# MainPCB.net
KiCad netlist of a schematic drawn in Altium Designer
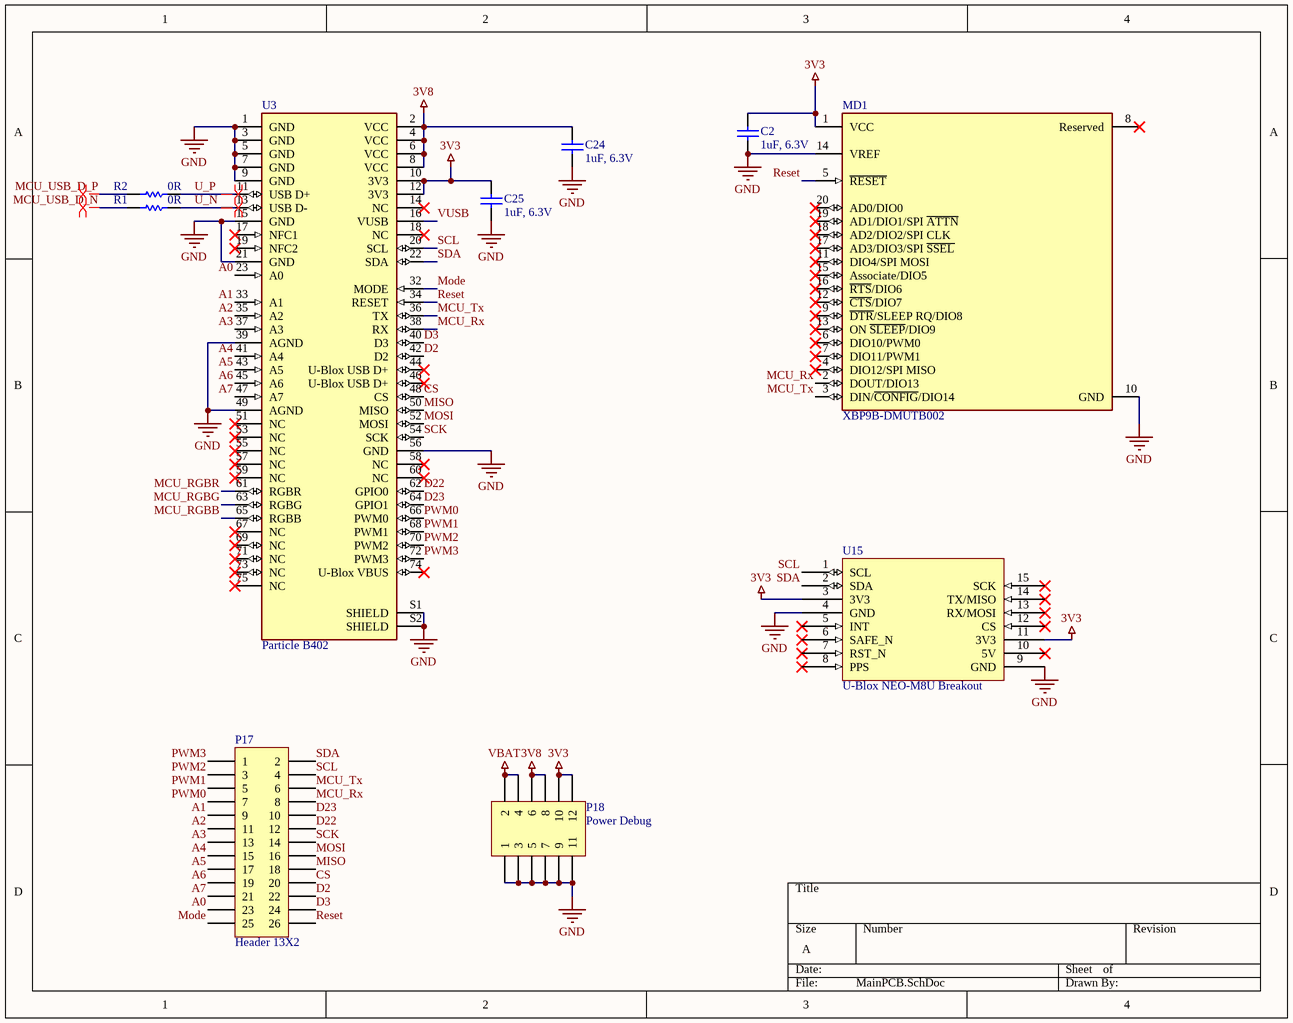
[diagram p0: MainPCB.SchDoc]

(export (version "E")
  (design (tool "Eeschema 10.0.6"))
  (components
    (comp (ref "C2")
      (value "1uF, 6.3V")
      (footprint "ANTC1608X90N")
      (description "Capacitor")
      (libsource (lib "Simulation Generic Components") (part "Capacitor"))
    )
    (comp (ref "C24")
      (value "1uF, 6.3V")
      (footprint "ANTC1608X90N")
      (description "Capacitor")
      (libsource (lib "Simulation Generic Components") (part "Capacitor"))
    )
    (comp (ref "C25")
      (value "1uF, 6.3V")
      (footprint "ANTC1608X90N")
      (description "Capacitor")
      (libsource (lib "Simulation Generic Components") (part "Capacitor"))
    )
    (comp (ref "MD1")
      (value "XBP9B-DMUTB002")
      (footprint "FP-XBP9B-DMUTB002-MFG")
      (description "RX TXRX MOD ISM < 1GHZ U.FL TH")
      (libsource (lib "Altium Content Vault") (part "053d8e65a610ce00d52093c0e212ca3"))
    )
    (comp (ref "P17")
      (value "Header 13X2")
      (footprint "HDR2X13")
      (description "Header, 13-Pin, Dual row")
      (fields (field (name "PUBLISHER") "Altium Limited"))
      (libsource (lib "Miscellaneous Connectors") (part "Header 13X2"))
    )
    (comp (ref "P18")
      (value "Power Debug")
      (footprint "HDR2X6")
      (description "Header, 6-Pin, Dual row")
      (fields (field (name "PUBLISHER") "Altium Limited"))
      (libsource (lib "Miscellaneous Connectors") (part "Header 6X2"))
    )
    (comp (ref "R1")
      (value "0R")
      (footprint "0603 Resistor")
      (description "Resistor")
      (libsource (lib "Simulation Generic Components") (part "Resistor"))
    )
    (comp (ref "R2")
      (value "0R")
      (footprint "0603 Resistor")
      (description "Resistor")
      (libsource (lib "Simulation Generic Components") (part "Resistor"))
    )
    (comp (ref "U3")
      (value "B402")
      (footprint "B402 Full")
      (description "Connector, Backplane, Housing, Receptacle, 67 Position, 2row")
      (fields (field (name "MP") "2199230-4") (field (name "SUPPLIER PART NUMBER 1") "Particle B402"))
      (libsource (lib "WaterNet23BotPCB") (part "B402"))
    )
    (comp (ref "U15")
      (value "U-Blox NEO-M8U Breakout")
      (footprint "U-Blox NEO-M8U")
      (description "GPS Board")
      (libsource (lib "WaterNet23BotPCB") (part "U-Blox NEO-M8U Breakout"))
    )
  )
  (nets
    (net (code "1") (name "/A0") (class "Default")
      (node (ref "P17") (pin "23") (pinfunction "23_23") (pintype "passive"))
      (node (ref "U3") (pin "23") (pinfunction "A0_23") (pintype "input"))
    )
    (net (code "2") (name "/A1") (class "Default")
      (node (ref "P17") (pin "9") (pinfunction "9_9") (pintype "passive"))
      (node (ref "U3") (pin "33") (pinfunction "A1_33") (pintype "input"))
    )
    (net (code "3") (name "/A2") (class "Default")
      (node (ref "P17") (pin "11") (pinfunction "11_11") (pintype "passive"))
      (node (ref "U3") (pin "35") (pinfunction "A2_35") (pintype "input"))
    )
    (net (code "4") (name "/A3") (class "Default")
      (node (ref "P17") (pin "13") (pinfunction "13_13") (pintype "passive"))
      (node (ref "U3") (pin "37") (pinfunction "A3_37") (pintype "input"))
    )
    (net (code "5") (name "/A4") (class "Default")
      (node (ref "P17") (pin "15") (pinfunction "15_15") (pintype "passive"))
      (node (ref "U3") (pin "41") (pinfunction "A4_41") (pintype "input"))
    )
    (net (code "6") (name "/A5") (class "Default")
      (node (ref "P17") (pin "17") (pinfunction "17_17") (pintype "passive"))
      (node (ref "U3") (pin "43") (pinfunction "A5_43") (pintype "input"))
    )
    (net (code "7") (name "/A6") (class "Default")
      (node (ref "P17") (pin "19") (pinfunction "19_19") (pintype "passive"))
      (node (ref "U3") (pin "45") (pinfunction "A6_45") (pintype "input"))
    )
    (net (code "8") (name "/A7") (class "Default")
      (node (ref "P17") (pin "21") (pinfunction "21_21") (pintype "passive"))
      (node (ref "U3") (pin "47") (pinfunction "A7_47") (pintype "input"))
    )
    (net (code "9") (name "/CS") (class "Default")
      (node (ref "P17") (pin "20") (pinfunction "20_20") (pintype "passive"))
      (node (ref "U3") (pin "48") (pinfunction "CS_48") (pintype "bidirectional"))
    )
    (net (code "10") (name "/D2") (class "Default")
      (node (ref "P17") (pin "22") (pinfunction "22_22") (pintype "passive"))
      (node (ref "U3") (pin "42") (pinfunction "D2_42") (pintype "bidirectional"))
    )
    (net (code "11") (name "/D3") (class "Default")
      (node (ref "P17") (pin "24") (pinfunction "24_24") (pintype "passive"))
      (node (ref "U3") (pin "40") (pinfunction "D3_40") (pintype "bidirectional"))
    )
    (net (code "12") (name "/D22") (class "Default")
      (node (ref "P17") (pin "12") (pinfunction "12_12") (pintype "passive"))
      (node (ref "U3") (pin "62") (pinfunction "GPIO0_62") (pintype "bidirectional"))
    )
    (net (code "13") (name "/D23") (class "Default")
      (node (ref "P17") (pin "10") (pinfunction "10_10") (pintype "passive"))
      (node (ref "U3") (pin "64") (pinfunction "GPIO1_64") (pintype "bidirectional"))
    )
    (net (code "14") (name "/MCU_RGBB") (class "Default")
      (node (ref "U3") (pin "65") (pinfunction "RGBB_65") (pintype "bidirectional"))
    )
    (net (code "15") (name "/MCU_RGBG") (class "Default")
      (node (ref "U3") (pin "63") (pinfunction "RGBG_63") (pintype "bidirectional"))
    )
    (net (code "16") (name "/MCU_RGBR") (class "Default")
      (node (ref "U3") (pin "61") (pinfunction "RGBR_61") (pintype "bidirectional"))
    )
    (net (code "17") (name "/MCU_Rx") (class "Default")
      (node (ref "MD1") (pin "2") (pinfunction "DOUT/DIO13_2") (pintype "bidirectional"))
      (node (ref "P17") (pin "8") (pinfunction "8_8") (pintype "passive"))
      (node (ref "U3") (pin "38") (pinfunction "RX_38") (pintype "bidirectional"))
    )
    (net (code "18") (name "/MCU_Tx") (class "Default")
      (node (ref "MD1") (pin "3") (pinfunction "DIN/~{CONFIG}/DIO14_3") (pintype "bidirectional"))
      (node (ref "P17") (pin "6") (pinfunction "6_6") (pintype "passive"))
      (node (ref "U3") (pin "36") (pinfunction "TX_36") (pintype "bidirectional"))
    )
    (net (code "19") (name "/MCU_USB_D_N") (class "Default")
      (node (ref "R1") (pin "1") (pinfunction "1_1") (pintype "passive"))
    )
    (net (code "20") (name "/MCU_USB_D_P") (class "Default")
      (node (ref "R2") (pin "1") (pinfunction "1_1") (pintype "passive"))
    )
    (net (code "21") (name "/MISO") (class "Default")
      (node (ref "P17") (pin "18") (pinfunction "18_18") (pintype "passive"))
      (node (ref "U3") (pin "50") (pinfunction "MISO_50") (pintype "bidirectional"))
    )
    (net (code "22") (name "/MOSI") (class "Default")
      (node (ref "P17") (pin "16") (pinfunction "16_16") (pintype "passive"))
      (node (ref "U3") (pin "52") (pinfunction "MOSI_52") (pintype "bidirectional"))
    )
    (net (code "23") (name "/Mode") (class "Default")
      (node (ref "P17") (pin "25") (pinfunction "25_25") (pintype "passive"))
      (node (ref "U3") (pin "32") (pinfunction "MODE_32") (pintype "input"))
    )
    (net (code "24") (name "/PWM0") (class "Default")
      (node (ref "P17") (pin "7") (pinfunction "7_7") (pintype "passive"))
      (node (ref "U3") (pin "66") (pinfunction "PWM0_66") (pintype "bidirectional"))
    )
    (net (code "25") (name "/PWM1") (class "Default")
      (node (ref "P17") (pin "5") (pinfunction "5_5") (pintype "passive"))
      (node (ref "U3") (pin "68") (pinfunction "PWM1_68") (pintype "bidirectional"))
    )
    (net (code "26") (name "/PWM2") (class "Default")
      (node (ref "P17") (pin "3") (pinfunction "3_3") (pintype "passive"))
      (node (ref "U3") (pin "70") (pinfunction "PWM2_70") (pintype "bidirectional"))
    )
    (net (code "27") (name "/PWM3") (class "Default")
      (node (ref "P17") (pin "1") (pinfunction "1_1") (pintype "passive"))
      (node (ref "U3") (pin "72") (pinfunction "PWM3_72") (pintype "bidirectional"))
    )
    (net (code "28") (name "/Reset") (class "Default")
      (node (ref "MD1") (pin "5") (pinfunction "~{RESET}_5") (pintype "input"))
      (node (ref "P17") (pin "26") (pinfunction "26_26") (pintype "passive"))
      (node (ref "U3") (pin "34") (pinfunction "RESET_34") (pintype "input"))
    )
    (net (code "29") (name "/SCK") (class "Default")
      (node (ref "P17") (pin "14") (pinfunction "14_14") (pintype "passive"))
      (node (ref "U3") (pin "54") (pinfunction "SCK_54") (pintype "bidirectional"))
    )
    (net (code "30") (name "/SCL") (class "Default")
      (node (ref "P17") (pin "4") (pinfunction "4_4") (pintype "passive"))
      (node (ref "U15") (pin "1") (pinfunction "SCL_1") (pintype "bidirectional"))
      (node (ref "U3") (pin "20") (pinfunction "SCL_20") (pintype "bidirectional"))
    )
    (net (code "31") (name "/SDA") (class "Default")
      (node (ref "P17") (pin "2") (pinfunction "2_2") (pintype "passive"))
      (node (ref "U15") (pin "2") (pinfunction "SDA_2") (pintype "bidirectional"))
      (node (ref "U3") (pin "22") (pinfunction "SDA_22") (pintype "bidirectional"))
    )
    (net (code "32") (name "/U_N") (class "Default")
      (node (ref "R1") (pin "2") (pinfunction "2_2") (pintype "passive"))
      (node (ref "U3") (pin "13") (pinfunction "USB_D-_13") (pintype "bidirectional"))
    )
    (net (code "33") (name "/U_P") (class "Default")
      (node (ref "R2") (pin "2") (pinfunction "2_2") (pintype "passive"))
      (node (ref "U3") (pin "11") (pinfunction "USB_D+_11") (pintype "bidirectional"))
    )
    (net (code "34") (name "/VUSB") (class "Default")
      (node (ref "U3") (pin "16") (pinfunction "VUSB_16") (pintype "power_in"))
    )
    (net (code "35") (name "3V3") (class "Default")
      (node (ref "C2") (pin "2") (pinfunction "2_2") (pintype "passive"))
      (node (ref "C25") (pin "2") (pinfunction "2_2") (pintype "passive"))
      (node (ref "MD1") (pin "1") (pinfunction "VCC_1") (pintype "power_in"))
      (node (ref "P18") (pin "10") (pinfunction "10_10") (pintype "passive"))
      (node (ref "P18") (pin "12") (pinfunction "12_12") (pintype "passive"))
      (node (ref "U15") (pin "11") (pinfunction "3V3_11") (pintype "power_in"))
      (node (ref "U15") (pin "3") (pinfunction "3V3_3") (pintype "power_in"))
      (node (ref "U3") (pin "10") (pinfunction "3V3_10") (pintype "power_in"))
      (node (ref "U3") (pin "12") (pinfunction "3V3_12") (pintype "power_in"))
    )
    (net (code "36") (name "3V8") (class "Default")
      (node (ref "C24") (pin "2") (pinfunction "2_2") (pintype "passive"))
      (node (ref "P18") (pin "6") (pinfunction "6_6") (pintype "passive"))
      (node (ref "P18") (pin "8") (pinfunction "8_8") (pintype "passive"))
      (node (ref "U3") (pin "2") (pinfunction "VCC_2") (pintype "power_in"))
      (node (ref "U3") (pin "4") (pinfunction "VCC_4") (pintype "power_in"))
      (node (ref "U3") (pin "6") (pinfunction "VCC_6") (pintype "power_in"))
      (node (ref "U3") (pin "8") (pinfunction "VCC_8") (pintype "power_in"))
    )
    (net (code "37") (name "GND") (class "Default")
      (node (ref "C2") (pin "1") (pinfunction "1_1") (pintype "passive"))
      (node (ref "C24") (pin "1") (pinfunction "1_1") (pintype "passive"))
      (node (ref "C25") (pin "1") (pinfunction "1_1") (pintype "passive"))
      (node (ref "MD1") (pin "10") (pinfunction "GND_10") (pintype "power_in"))
      (node (ref "MD1") (pin "14") (pinfunction "VREF_14") (pintype "passive"))
      (node (ref "P18") (pin "1") (pinfunction "1_1") (pintype "passive"))
      (node (ref "P18") (pin "11") (pinfunction "11_11") (pintype "passive"))
      (node (ref "P18") (pin "3") (pinfunction "3_3") (pintype "passive"))
      (node (ref "P18") (pin "5") (pinfunction "5_5") (pintype "passive"))
      (node (ref "P18") (pin "7") (pinfunction "7_7") (pintype "passive"))
      (node (ref "P18") (pin "9") (pinfunction "9_9") (pintype "passive"))
      (node (ref "U15") (pin "4") (pinfunction "GND_4") (pintype "power_in"))
      (node (ref "U15") (pin "9") (pinfunction "GND_9") (pintype "power_in"))
      (node (ref "U3") (pin "1") (pinfunction "GND_1") (pintype "power_in"))
      (node (ref "U3") (pin "15") (pinfunction "GND_15") (pintype "power_in"))
      (node (ref "U3") (pin "21") (pinfunction "GND_21") (pintype "power_in"))
      (node (ref "U3") (pin "3") (pinfunction "GND_3") (pintype "power_in"))
      (node (ref "U3") (pin "39") (pinfunction "AGND_39") (pintype "power_in"))
      (node (ref "U3") (pin "49") (pinfunction "AGND_49") (pintype "power_in"))
      (node (ref "U3") (pin "5") (pinfunction "GND_5") (pintype "power_in"))
      (node (ref "U3") (pin "56") (pinfunction "GND_56") (pintype "power_in"))
      (node (ref "U3") (pin "7") (pinfunction "GND_7") (pintype "power_in"))
      (node (ref "U3") (pin "9") (pinfunction "GND_9") (pintype "power_in"))
      (node (ref "U3") (pin "S1") (pinfunction "SHIELD_S1") (pintype "passive"))
      (node (ref "U3") (pin "S2") (pinfunction "SHIELD_S2") (pintype "passive"))
    )
    (net (code "38") (name "VBAT") (class "Default")
      (node (ref "P18") (pin "2") (pinfunction "2_2") (pintype "passive"))
      (node (ref "P18") (pin "4") (pinfunction "4_4") (pintype "passive"))
    )
    (net (code "39") (name "unconnected-(MD1-AD0{slash}DIO0-Pad20)") (class "Default")
      (node (ref "MD1") (pin "20") (pinfunction "AD0/DIO0_20") (pintype "bidirectional+no_connect"))
    )
    (net (code "40") (name "unconnected-(MD1-AD1{slash}DIO1{slash}SPI_~{ATTN}-Pad19)") (class "Default")
      (node (ref "MD1") (pin "19") (pinfunction "AD1/DIO1/SPI_~{ATTN}_19") (pintype "bidirectional+no_connect"))
    )
    (net (code "41") (name "unconnected-(MD1-AD2{slash}DIO2{slash}SPI_CLK-Pad18)") (class "Default")
      (node (ref "MD1") (pin "18") (pinfunction "AD2/DIO2/SPI_CLK_18") (pintype "bidirectional+no_connect"))
    )
    (net (code "42") (name "unconnected-(MD1-AD3{slash}DIO3{slash}SPI_~{SSEL}-Pad17)") (class "Default")
      (node (ref "MD1") (pin "17") (pinfunction "AD3/DIO3/SPI_~{SSEL}_17") (pintype "bidirectional+no_connect"))
    )
    (net (code "43") (name "unconnected-(MD1-Associate{slash}DIO5-Pad15)") (class "Default")
      (node (ref "MD1") (pin "15") (pinfunction "Associate/DIO5_15") (pintype "bidirectional+no_connect"))
    )
    (net (code "44") (name "unconnected-(MD1-DIO4{slash}SPI_MOSI-Pad11)") (class "Default")
      (node (ref "MD1") (pin "11") (pinfunction "DIO4/SPI_MOSI_11") (pintype "bidirectional+no_connect"))
    )
    (net (code "45") (name "unconnected-(MD1-DIO10{slash}PWM0-Pad6)") (class "Default")
      (node (ref "MD1") (pin "6") (pinfunction "DIO10/PWM0_6") (pintype "bidirectional+no_connect"))
    )
    (net (code "46") (name "unconnected-(MD1-DIO11{slash}PWM1-Pad7)") (class "Default")
      (node (ref "MD1") (pin "7") (pinfunction "DIO11/PWM1_7") (pintype "bidirectional+no_connect"))
    )
    (net (code "47") (name "unconnected-(MD1-DIO12{slash}SPI_MISO-Pad4)") (class "Default")
      (node (ref "MD1") (pin "4") (pinfunction "DIO12/SPI_MISO_4") (pintype "bidirectional+no_connect"))
    )
    (net (code "48") (name "unconnected-(MD1-ON_~{SLEEP}{slash}DIO9-Pad13)") (class "Default")
      (node (ref "MD1") (pin "13") (pinfunction "ON_~{SLEEP}/DIO9_13") (pintype "bidirectional+no_connect"))
    )
    (net (code "49") (name "unconnected-(MD1-Reserved-Pad8)") (class "Default")
      (node (ref "MD1") (pin "8") (pinfunction "Reserved_8") (pintype "passive+no_connect"))
    )
    (net (code "50") (name "unconnected-(MD1-~{CTS}{slash}DIO7-Pad12)") (class "Default")
      (node (ref "MD1") (pin "12") (pinfunction "~{CTS}/DIO7_12") (pintype "bidirectional+no_connect"))
    )
    (net (code "51") (name "unconnected-(MD1-~{DTR}{slash}SLEEP_RQ{slash}DIO8-Pad9)") (class "Default")
      (node (ref "MD1") (pin "9") (pinfunction "~{DTR}/SLEEP_RQ/DIO8_9") (pintype "bidirectional+no_connect"))
    )
    (net (code "52") (name "unconnected-(MD1-~{RTS}{slash}DIO6-Pad16)") (class "Default")
      (node (ref "MD1") (pin "16") (pinfunction "~{RTS}/DIO6_16") (pintype "bidirectional+no_connect"))
    )
    (net (code "53") (name "unconnected-(U3-NC-Pad14)") (class "Default")
      (node (ref "U3") (pin "14") (pinfunction "NC_14") (pintype "tri_state+no_connect"))
    )
    (net (code "54") (name "unconnected-(U3-NC-Pad18)") (class "Default")
      (node (ref "U3") (pin "18") (pinfunction "NC_18") (pintype "tri_state+no_connect"))
    )
    (net (code "55") (name "unconnected-(U3-NC-Pad51)") (class "Default")
      (node (ref "U3") (pin "51") (pinfunction "NC_51") (pintype "tri_state+no_connect"))
    )
    (net (code "56") (name "unconnected-(U3-NC-Pad53)") (class "Default")
      (node (ref "U3") (pin "53") (pinfunction "NC_53") (pintype "tri_state+no_connect"))
    )
    (net (code "57") (name "unconnected-(U3-NC-Pad55)") (class "Default")
      (node (ref "U3") (pin "55") (pinfunction "NC_55") (pintype "tri_state+no_connect"))
    )
    (net (code "58") (name "unconnected-(U3-NC-Pad57)") (class "Default")
      (node (ref "U3") (pin "57") (pinfunction "NC_57") (pintype "tri_state+no_connect"))
    )
    (net (code "59") (name "unconnected-(U3-NC-Pad58)") (class "Default")
      (node (ref "U3") (pin "58") (pinfunction "NC_58") (pintype "tri_state+no_connect"))
    )
    (net (code "60") (name "unconnected-(U3-NC-Pad59)") (class "Default")
      (node (ref "U3") (pin "59") (pinfunction "NC_59") (pintype "tri_state+no_connect"))
    )
    (net (code "61") (name "unconnected-(U3-NC-Pad60)") (class "Default")
      (node (ref "U3") (pin "60") (pinfunction "NC_60") (pintype "tri_state+no_connect"))
    )
    (net (code "62") (name "unconnected-(U3-NC-Pad67)") (class "Default")
      (node (ref "U3") (pin "67") (pinfunction "NC_67") (pintype "power_in+no_connect"))
    )
    (net (code "63") (name "unconnected-(U3-NC-Pad69)") (class "Default")
      (node (ref "U3") (pin "69") (pinfunction "NC_69") (pintype "bidirectional+no_connect"))
    )
    (net (code "64") (name "unconnected-(U3-NC-Pad71)") (class "Default")
      (node (ref "U3") (pin "71") (pinfunction "NC_71") (pintype "bidirectional+no_connect"))
    )
    (net (code "65") (name "unconnected-(U3-NC-Pad73)") (class "Default")
      (node (ref "U3") (pin "73") (pinfunction "NC_73") (pintype "bidirectional+no_connect"))
    )
    (net (code "66") (name "unconnected-(U3-NC-Pad75)") (class "Default")
      (node (ref "U3") (pin "75") (pinfunction "NC_75") (pintype "tri_state+no_connect"))
    )
    (net (code "67") (name "unconnected-(U3-NFC1-Pad17)") (class "Default")
      (node (ref "U3") (pin "17") (pinfunction "NFC1_17") (pintype "input+no_connect"))
    )
    (net (code "68") (name "unconnected-(U3-NFC2-Pad19)") (class "Default")
      (node (ref "U3") (pin "19") (pinfunction "NFC2_19") (pintype "input+no_connect"))
    )
    (net (code "69") (name "unconnected-(U3-U-Blox_USB_D+-Pad44)") (class "Default")
      (node (ref "U3") (pin "44") (pinfunction "U-Blox_USB_D+_44") (pintype "bidirectional+no_connect"))
    )
    (net (code "70") (name "unconnected-(U3-U-Blox_USB_D+-Pad46)") (class "Default")
      (node (ref "U3") (pin "46") (pinfunction "U-Blox_USB_D+_46") (pintype "bidirectional+no_connect"))
    )
    (net (code "71") (name "unconnected-(U3-U-Blox_VBUS-Pad74)") (class "Default")
      (node (ref "U3") (pin "74") (pinfunction "U-Blox_VBUS_74") (pintype "bidirectional+no_connect"))
    )
    (net (code "72") (name "unconnected-(U15-5V-Pad10)") (class "Default")
      (node (ref "U15") (pin "10") (pinfunction "5V_10") (pintype "power_in+no_connect"))
    )
    (net (code "73") (name "unconnected-(U15-CS-Pad12)") (class "Default")
      (node (ref "U15") (pin "12") (pinfunction "CS_12") (pintype "input+no_connect"))
    )
    (net (code "74") (name "unconnected-(U15-INT-Pad5)") (class "Default")
      (node (ref "U15") (pin "5") (pinfunction "INT_5") (pintype "input+no_connect"))
    )
    (net (code "75") (name "unconnected-(U15-PPS-Pad8)") (class "Default")
      (node (ref "U15") (pin "8") (pinfunction "PPS_8") (pintype "input+no_connect"))
    )
    (net (code "76") (name "unconnected-(U15-RST_N-Pad7)") (class "Default")
      (node (ref "U15") (pin "7") (pinfunction "RST_N_7") (pintype "input+no_connect"))
    )
    (net (code "77") (name "unconnected-(U15-RX{slash}MOSI-Pad13)") (class "Default")
      (node (ref "U15") (pin "13") (pinfunction "RX/MOSI_13") (pintype "input+no_connect"))
    )
    (net (code "78") (name "unconnected-(U15-SAFE_N-Pad6)") (class "Default")
      (node (ref "U15") (pin "6") (pinfunction "SAFE_N_6") (pintype "input+no_connect"))
    )
    (net (code "79") (name "unconnected-(U15-SCK-Pad15)") (class "Default")
      (node (ref "U15") (pin "15") (pinfunction "SCK_15") (pintype "input+no_connect"))
    )
    (net (code "80") (name "unconnected-(U15-TX{slash}MISO-Pad14)") (class "Default")
      (node (ref "U15") (pin "14") (pinfunction "TX/MISO_14") (pintype "input+no_connect"))
    )
  )
)
